# Sheet5.net
KiCad netlist of a schematic drawn in Altium Designer
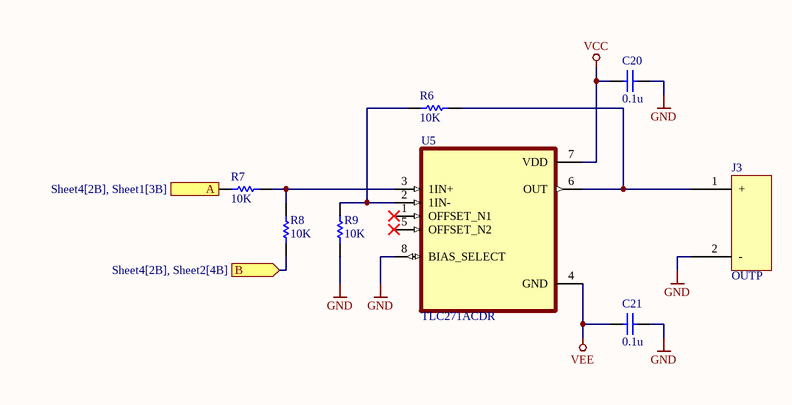
[diagram p0: Sheet5.SchDoc]

(export (version "E")
  (design (tool "Eeschema 10.0.6"))
  (components
    (comp (ref "C20")
      (value "0.1u")
      (footprint "CAPC2012X150N")
      (description "Capacitor")
      (libsource (lib "Simulation Generic Components") (part "Capacitor"))
    )
    (comp (ref "C21")
      (value "0.1u")
      (footprint "CAPC2012X150N")
      (description "Capacitor")
      (libsource (lib "Simulation Generic Components") (part "Capacitor"))
    )
    (comp (ref "J3")
      (value "OUTP")
      (footprint "JST_B2B-XH-A_(LF)(SN)")
      (libsource (lib "Schlib1") (part "Outp"))
    )
    (comp (ref "R6")
      (value "10K")
      (footprint "RES_ERA6AHD330V")
      (description "Resistor")
      (libsource (lib "Simulation Generic Components") (part "Resistor"))
    )
    (comp (ref "R7")
      (value "10K")
      (footprint "RES_ERA6AHD330V")
      (description "Resistor")
      (libsource (lib "Simulation Generic Components") (part "Resistor"))
    )
    (comp (ref "R8")
      (value "10K")
      (footprint "RES_ERA6AHD330V")
      (description "Resistor")
      (libsource (lib "Simulation Generic Components") (part "Resistor"))
    )
    (comp (ref "R9")
      (value "10K")
      (footprint "RES_ERA6AHD330V")
      (description "Resistor")
      (libsource (lib "Simulation Generic Components") (part "Resistor"))
    )
    (comp (ref "U5")
      (value "TLC271ACDR")
      (footprint "SOIC127P599X175-8N")
      (description "Single, 16-V, 2-MHz, 5-mV offset voltage, In to V- operational amplifier")
      (fields (field (name "MF") "Texas Instruments"))
      (libsource (lib "TLC271ACDR") (part "TLC271ACDR"))
    )
  )
  (nets
    (net (code "1") (name "/A") (class "Default")
      (node (ref "R7") (pin "2") (pinfunction "2_2") (pintype "passive"))
    )
    (net (code "2") (name "/B") (class "Default")
      (node (ref "R8") (pin "1") (pinfunction "1_1") (pintype "passive"))
    )
    (net (code "3") (name "GND") (class "Default")
      (node (ref "C20") (pin "1") (pinfunction "1_1") (pintype "passive"))
      (node (ref "C21") (pin "1") (pinfunction "1_1") (pintype "passive"))
      (node (ref "J3") (pin "2") (pinfunction "-_2") (pintype "passive"))
      (node (ref "R9") (pin "1") (pinfunction "1_1") (pintype "passive"))
      (node (ref "U5") (pin "8") (pinfunction "BIAS_SELECT_8") (pintype "bidirectional"))
    )
    (net (code "4") (name "Net-(J3-+)") (class "Default")
      (node (ref "J3") (pin "1") (pinfunction "+_1") (pintype "passive"))
      (node (ref "R6") (pin "2") (pinfunction "2_2") (pintype "passive"))
      (node (ref "U5") (pin "6") (pinfunction "OUT_6") (pintype "output"))
    )
    (net (code "5") (name "Net-(U5-1IN+)") (class "Default")
      (node (ref "R7") (pin "1") (pinfunction "1_1") (pintype "passive"))
      (node (ref "R8") (pin "2") (pinfunction "2_2") (pintype "passive"))
      (node (ref "U5") (pin "3") (pinfunction "1IN+_3") (pintype "input"))
    )
    (net (code "6") (name "Net-(U5-1IN-)") (class "Default")
      (node (ref "R6") (pin "1") (pinfunction "1_1") (pintype "passive"))
      (node (ref "R9") (pin "2") (pinfunction "2_2") (pintype "passive"))
      (node (ref "U5") (pin "2") (pinfunction "1IN-_2") (pintype "input"))
    )
    (net (code "7") (name "VCC") (class "Default")
      (node (ref "C20") (pin "2") (pinfunction "2_2") (pintype "passive"))
      (node (ref "U5") (pin "7") (pinfunction "VDD_7") (pintype "power_in"))
    )
    (net (code "8") (name "VEE") (class "Default")
      (node (ref "C21") (pin "2") (pinfunction "2_2") (pintype "passive"))
      (node (ref "U5") (pin "4") (pinfunction "GND_4") (pintype "power_in"))
    )
    (net (code "9") (name "unconnected-(U5-OFFSET_N1-Pad1)") (class "Default")
      (node (ref "U5") (pin "1") (pinfunction "OFFSET_N1_1") (pintype "input+no_connect"))
    )
    (net (code "10") (name "unconnected-(U5-OFFSET_N2-Pad5)") (class "Default")
      (node (ref "U5") (pin "5") (pinfunction "OFFSET_N2_5") (pintype "input+no_connect"))
    )
  )
)
